# IndicatorControl.net
KiCad netlist of a schematic drawn in Altium Designer
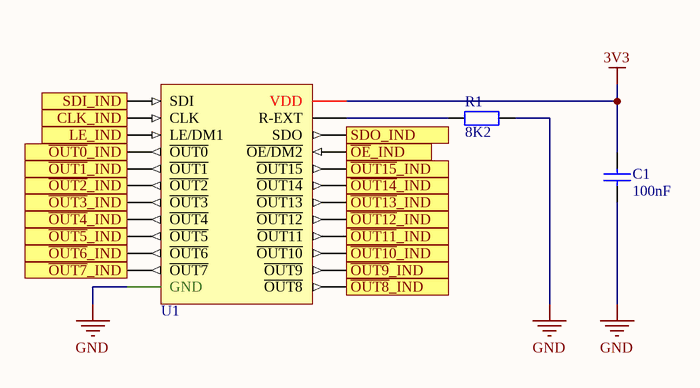
[diagram p0: IndicatorControl.SchDoc]

(export (version "E")
  (design (tool "Eeschema 10.0.6"))
  (components
    (comp (ref "C1")
      (value "100nF")
      (footprint "FP_0805_CAP_085")
      (description "Capacitor")
      (fields (field (name "TOLERANCE") "+80%/-20%") (field (name "VOLTAGE") "25V"))
      (libsource (lib "hallglib") (part "CAP 100nF"))
    )
    (comp (ref "R1")
      (value "8K2")
      (footprint "FP_0805_RES")
      (description "Resistor")
      (fields (field (name "TOLERANCE") "5%") (field (name "POWER") "125mW"))
      (libsource (lib "hallglib") (part "RES 8K2"))
    )
    (comp (ref "U1")
      (value "STP16CP05TTR")
      (footprint "24-Pin TSSOP")
      (description "Led Driver, 16 Outputs, Constant Current, 3V-5.5V in, 30MHz switch, 20V/100mA out, TSSOP-24")
      (libsource (lib "RobonAUT") (part "STP16CP05TTR"))
    )
  )
  (nets
    (net (code "1") (name "/CLK_IND") (class "Default")
      (node (ref "U1") (pin "3") (pinfunction "CLK_3") (pintype "input"))
    )
    (net (code "2") (name "/LE_IND") (class "Default")
      (node (ref "U1") (pin "4") (pinfunction "LE/DM1_4") (pintype "input"))
    )
    (net (code "3") (name "/SDI_IND") (class "Default")
      (node (ref "U1") (pin "2") (pinfunction "SDI_2") (pintype "input"))
    )
    (net (code "4") (name "/SDO_IND") (class "Default")
      (node (ref "U1") (pin "22") (pinfunction "SDO_22") (pintype "output"))
    )
    (net (code "5") (name "/~{OE}_IND") (class "Default")
      (node (ref "U1") (pin "21") (pinfunction "~{OE/DM2}_21") (pintype "input"))
    )
    (net (code "6") (name "/~{OUT0}_IND") (class "Default")
      (node (ref "U1") (pin "5") (pinfunction "~{OUT0}_5") (pintype "output"))
    )
    (net (code "7") (name "/~{OUT1}_IND") (class "Default")
      (node (ref "U1") (pin "6") (pinfunction "~{OUT1}_6") (pintype "output"))
    )
    (net (code "8") (name "/~{OUT2}_IND") (class "Default")
      (node (ref "U1") (pin "7") (pinfunction "~{OUT2}_7") (pintype "output"))
    )
    (net (code "9") (name "/~{OUT3}_IND") (class "Default")
      (node (ref "U1") (pin "8") (pinfunction "~{OUT3}_8") (pintype "output"))
    )
    (net (code "10") (name "/~{OUT4}_IND") (class "Default")
      (node (ref "U1") (pin "9") (pinfunction "~{OUT4}_9") (pintype "output"))
    )
    (net (code "11") (name "/~{OUT5}_IND") (class "Default")
      (node (ref "U1") (pin "10") (pinfunction "~{OUT5}_10") (pintype "output"))
    )
    (net (code "12") (name "/~{OUT6}_IND") (class "Default")
      (node (ref "U1") (pin "11") (pinfunction "~{OUT6}_11") (pintype "output"))
    )
    (net (code "13") (name "/~{OUT7}_IND") (class "Default")
      (node (ref "U1") (pin "12") (pinfunction "~{OUT7}_12") (pintype "output"))
    )
    (net (code "14") (name "/~{OUT8}_IND") (class "Default")
      (node (ref "U1") (pin "13") (pinfunction "~{OUT8}_13") (pintype "output"))
    )
    (net (code "15") (name "/~{OUT9}_IND") (class "Default")
      (node (ref "U1") (pin "14") (pinfunction "~{OUT9}_14") (pintype "output"))
    )
    (net (code "16") (name "/~{OUT10}_IND") (class "Default")
      (node (ref "U1") (pin "15") (pinfunction "~{OUT10}_15") (pintype "output"))
    )
    (net (code "17") (name "/~{OUT11}_IND") (class "Default")
      (node (ref "U1") (pin "16") (pinfunction "~{OUT11}_16") (pintype "output"))
    )
    (net (code "18") (name "/~{OUT12}_IND") (class "Default")
      (node (ref "U1") (pin "17") (pinfunction "~{OUT12}_17") (pintype "output"))
    )
    (net (code "19") (name "/~{OUT13}_IND") (class "Default")
      (node (ref "U1") (pin "18") (pinfunction "~{OUT13}_18") (pintype "output"))
    )
    (net (code "20") (name "/~{OUT14}_IND") (class "Default")
      (node (ref "U1") (pin "19") (pinfunction "~{OUT14}_19") (pintype "output"))
    )
    (net (code "21") (name "/~{OUT15}_IND") (class "Default")
      (node (ref "U1") (pin "20") (pinfunction "~{OUT15}_20") (pintype "output"))
    )
    (net (code "22") (name "3V3") (class "Default")
      (node (ref "C1") (pin "2") (pinfunction "2_2") (pintype "passive"))
      (node (ref "U1") (pin "24") (pinfunction "VDD_24") (pintype "power_in"))
    )
    (net (code "23") (name "GND") (class "Default")
      (node (ref "C1") (pin "1") (pinfunction "1_1") (pintype "passive"))
      (node (ref "R1") (pin "2") (pinfunction "2_2") (pintype "passive"))
      (node (ref "U1") (pin "1") (pinfunction "GND_1") (pintype "power_in"))
    )
    (net (code "24") (name "Net-(U1-R-EXT)") (class "Default")
      (node (ref "R1") (pin "1") (pinfunction "1_1") (pintype "passive"))
      (node (ref "U1") (pin "23") (pinfunction "R-EXT_23") (pintype "passive"))
    )
  )
)
